# Tilt-A-Whirl_RPI-1031.net
KiCad netlist of a schematic drawn in EAGLE
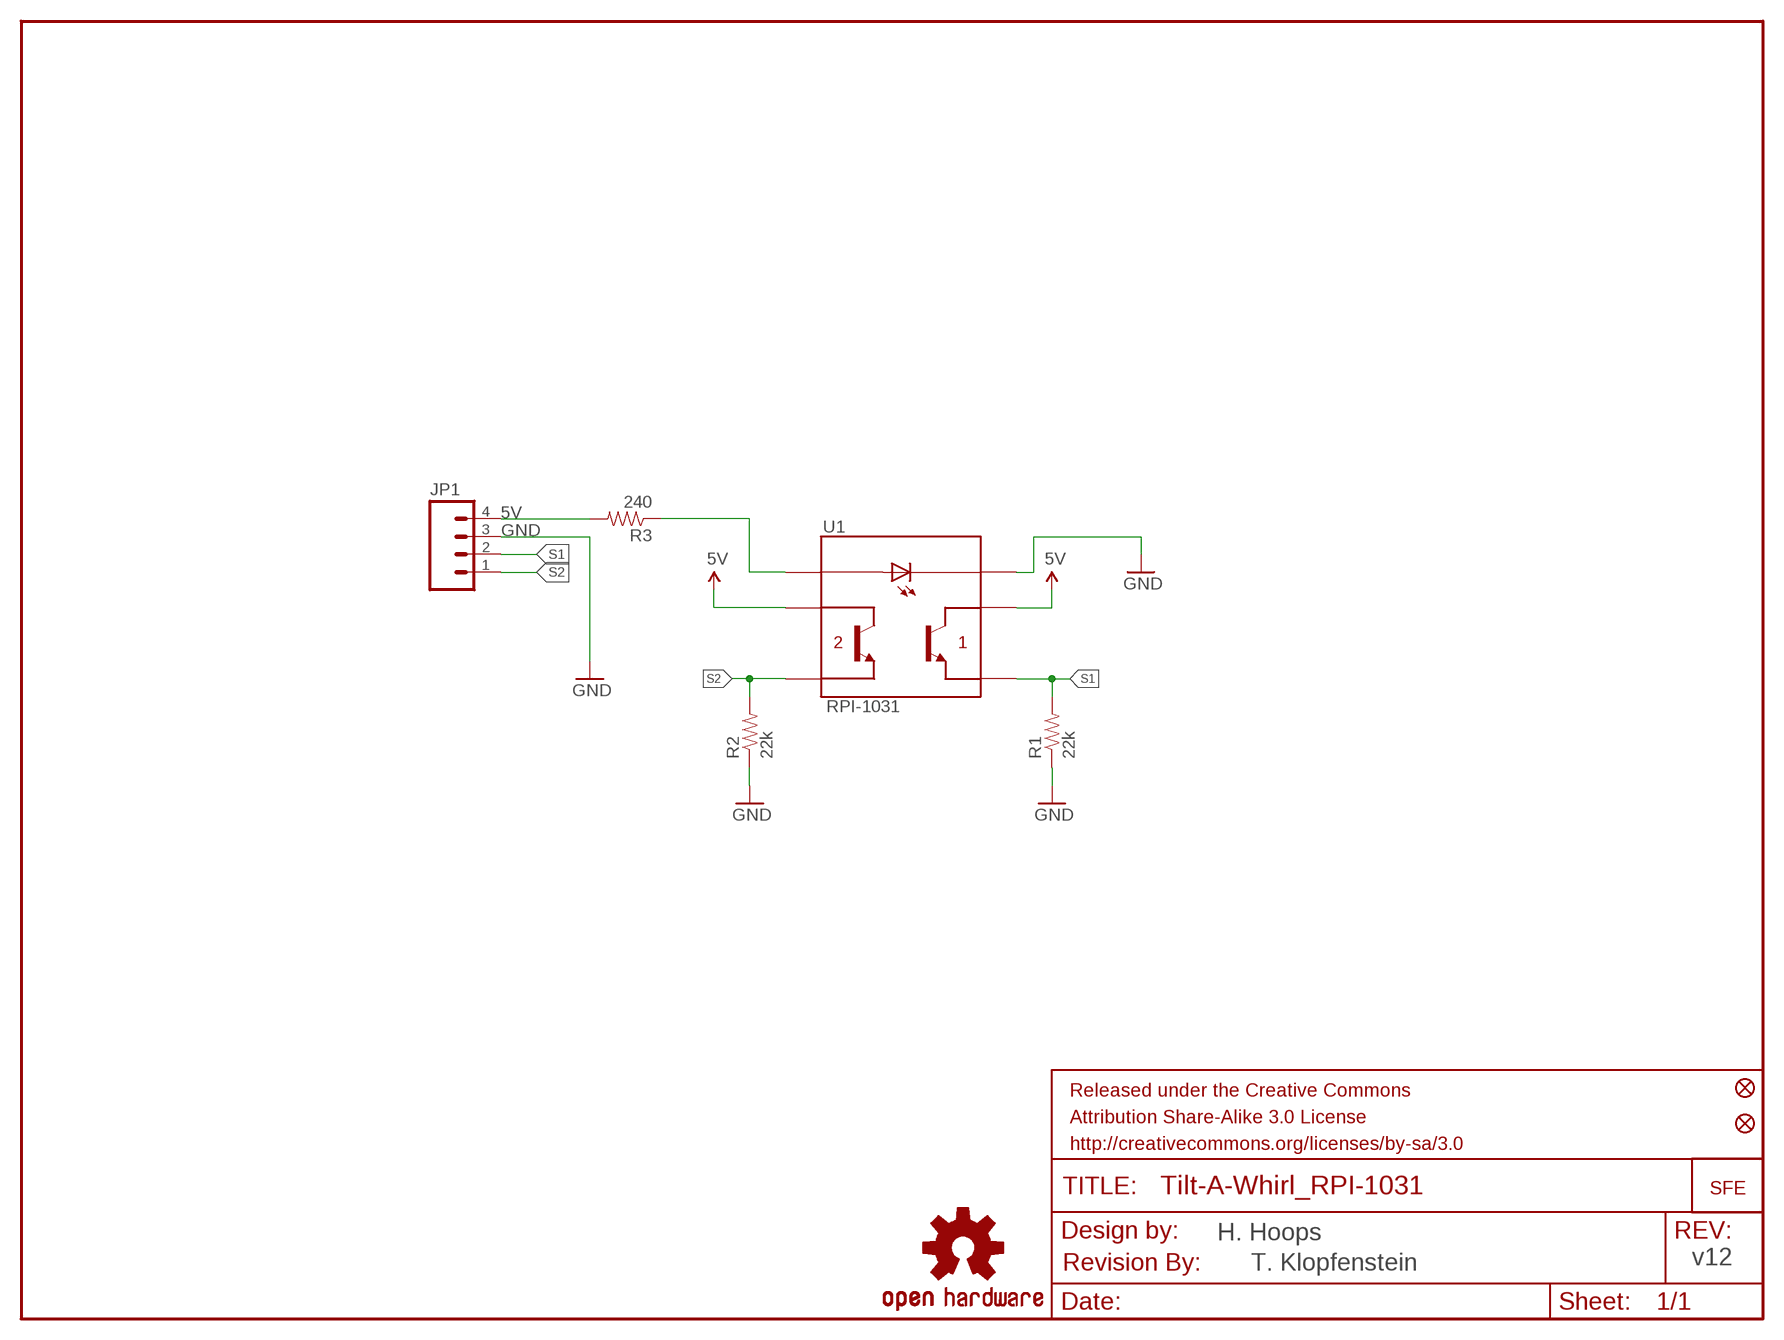
[diagram p0: schematic, sheet 1]

(export (version "E")
  (design (tool "Eeschema 10.0.6"))
  (components
    (comp (ref "FRAME1")
      (value "FRAME-LETTER")
      (footprint "eagle-import:CREATIVE_COMMONS")
      (libsource (lib "eagle-import") (part "FRAME-LETTER"))
    )
    (comp (ref "JP1")
      (value "M04PTH")
      (footprint "eagle-import:1X04")
      (libsource (lib "eagle-import") (part "M04PTH"))
    )
    (comp (ref "JP2")
      (value "FIDUCIAL1X2.5")
      (footprint "eagle-import:FIDUCIAL-1X2.5")
      (libsource (lib "eagle-import") (part "FIDUCIAL1X2.5"))
    )
    (comp (ref "JP3")
      (value "FIDUCIAL1X2.5")
      (footprint "eagle-import:FIDUCIAL-1X2.5")
      (libsource (lib "eagle-import") (part "FIDUCIAL1X2.5"))
    )
    (comp (ref "JP4")
      (value "LOGO-SFESK")
      (footprint "eagle-import:SFE-LOGO-FLAME")
      (libsource (lib "eagle-import") (part "LOGO-SFESK"))
    )
    (comp (ref "R1")
      (value "22k")
      (footprint "eagle-import:0603-RES")
      (libsource (lib "eagle-import") (part "22KOHM1/10W1%(0603)"))
    )
    (comp (ref "R2")
      (value "22k")
      (footprint "eagle-import:0603-RES")
      (libsource (lib "eagle-import") (part "22KOHM1/10W1%(0603)"))
    )
    (comp (ref "R3")
      (value "240")
      (footprint "eagle-import:0603-RES")
      (libsource (lib "eagle-import") (part "240OHM1/10W1%(0603)"))
    )
    (comp (ref "U$1")
      (value "OSHW-LOGOS")
      (footprint "eagle-import:OSHW-LOGO-S")
      (libsource (lib "eagle-import") (part "OSHW-LOGOS"))
    )
    (comp (ref "U$2")
      (value "REVISION")
      (footprint "eagle-import:REVISION")
      (libsource (lib "eagle-import") (part "REVISION"))
    )
    (comp (ref "U1")
      (value "RPI-1031")
      (footprint "eagle-import:RPI-1031")
      (libsource (lib "eagle-import") (part "RPI-1031"))
    )
  )
  (nets
    (net (code "1") (name "5V") (class "Default")
      (node (ref "JP1") (pin "4") (pinfunction "4_4") (pintype "passive"))
      (node (ref "R3") (pin "2") (pinfunction "2_2") (pintype "passive"))
      (node (ref "U1") (pin "2") (pinfunction "C1_2") (pintype "passive"))
      (node (ref "U1") (pin "5") (pinfunction "C2_5") (pintype "passive"))
    )
    (net (code "2") (name "GND") (class "Default")
      (node (ref "JP1") (pin "3") (pinfunction "3_3") (pintype "passive"))
      (node (ref "R1") (pin "1") (pinfunction "1_1") (pintype "passive"))
      (node (ref "R2") (pin "1") (pinfunction "1_1") (pintype "passive"))
      (node (ref "U1") (pin "3") (pinfunction "CATHODE_3") (pintype "passive"))
    )
    (net (code "3") (name "Net-(U1-ANODE)") (class "Default")
      (node (ref "R3") (pin "1") (pinfunction "1_1") (pintype "passive"))
      (node (ref "U1") (pin "6") (pinfunction "ANODE_6") (pintype "passive"))
    )
    (net (code "4") (name "S1") (class "Default")
      (node (ref "JP1") (pin "2") (pinfunction "2_2") (pintype "passive"))
      (node (ref "R1") (pin "2") (pinfunction "2_2") (pintype "passive"))
      (node (ref "U1") (pin "1") (pinfunction "E1_1") (pintype "passive"))
    )
    (net (code "5") (name "S2") (class "Default")
      (node (ref "JP1") (pin "1") (pinfunction "1_1") (pintype "passive"))
      (node (ref "R2") (pin "2") (pinfunction "2_2") (pintype "passive"))
      (node (ref "U1") (pin "4") (pinfunction "E2_4") (pintype "passive"))
    )
  )
)
